# Sensors5V.net
KiCad netlist of a schematic drawn in Altium Designer
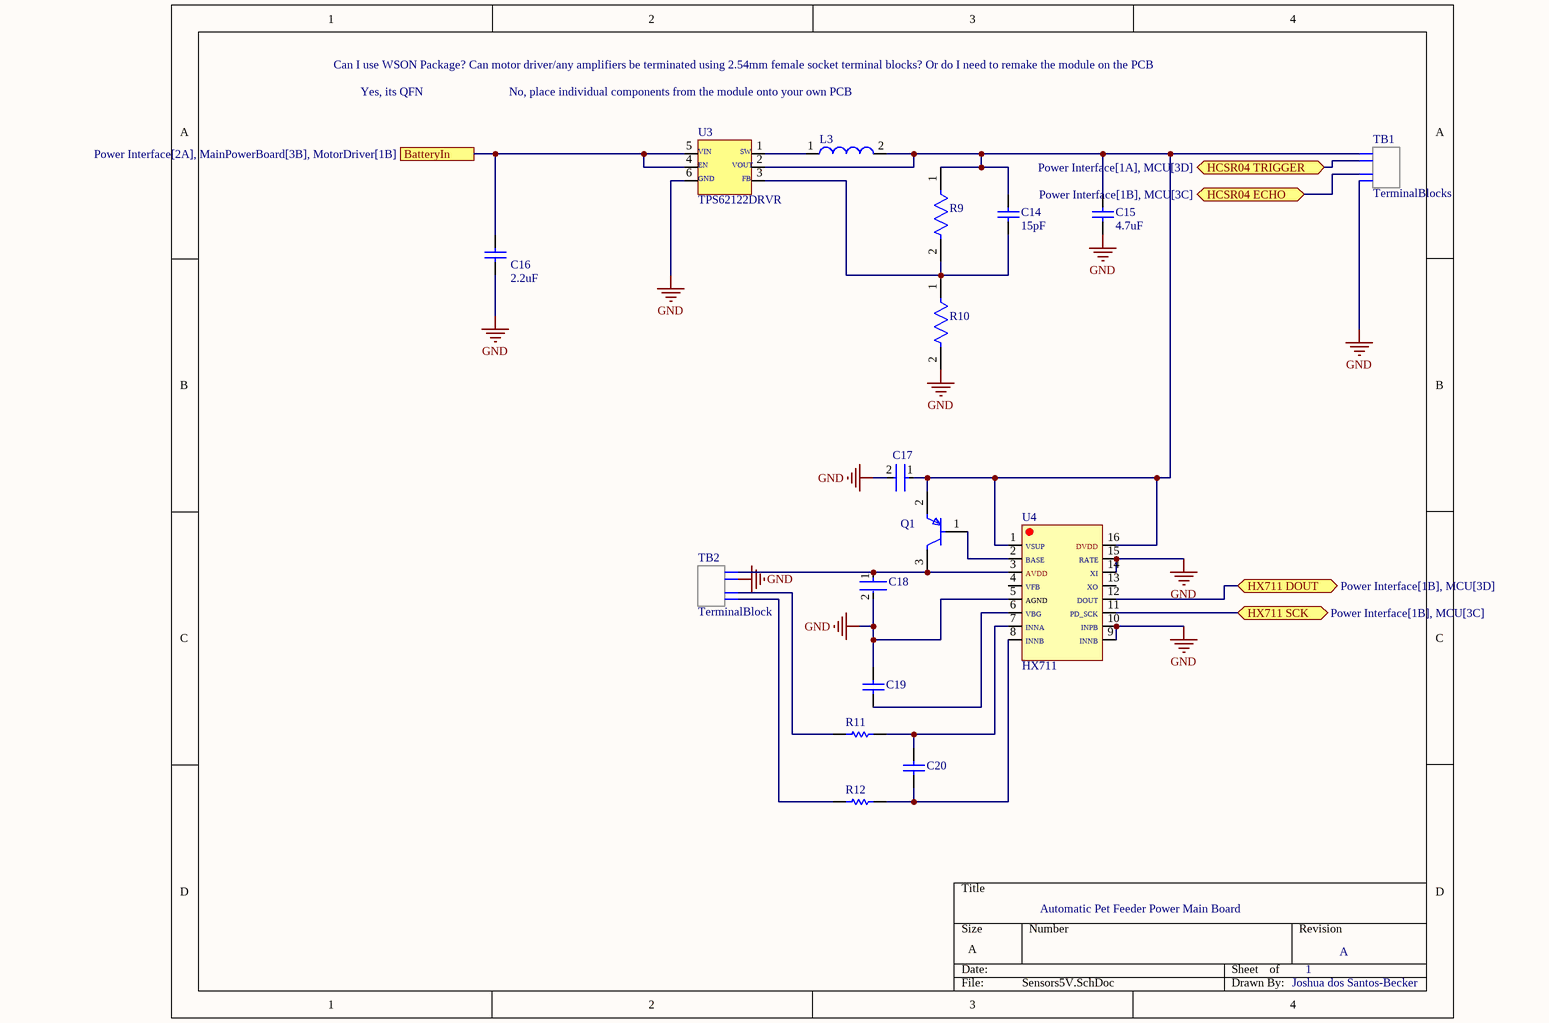
[diagram p0: Sensors5V.SchDoc]

(export (version "E")
  (design (tool "Eeschema 10.0.6"))
  (components
    (comp (ref "C14")
      (value "15pF")
      (footprint "CAP_0805")
      (description "CC0805JRNPO9BN150")
      (libsource (lib "gsl") (part "Cff"))
    )
    (comp (ref "C15")
      (value "4.7uF")
      (footprint "CAPC1005X06N")
      (description "GRM155R61A475MEAAD")
      (libsource (lib "gsl") (part "Cout2"))
    )
    (comp (ref "C16")
      (value "2.2uF")
      (footprint "CAPC0402X02N")
      (description "C1005X5R1V225K050BC")
      (libsource (lib "gsl") (part "Cin2"))
    )
    (comp (ref "C17")
      (value "GRM21BR61C106KE15L")
      (footprint "FP-GRM21B-0_1-IPC_C")
      (description "Chip Multilayer Ceramic Capacitors for General Purpose, 0805, 10uF, X5R, 15%, 10%, 16V")
      (fields (field (name "TOLERANCE") "10%") (field (name "VOLTAGE") "16V"))
      (libsource (lib "Altium Content Vault") (part "b4654b650e69147ec39a6b967a45e02"))
    )
    (comp (ref "C18")
      (value "GRM21BR61C106KE15L")
      (footprint "FP-GRM21B-0_1-IPC_C")
      (description "Chip Multilayer Ceramic Capacitors for General Purpose, 0805, 10uF, X5R, 15%, 10%, 16V")
      (fields (field (name "TOLERANCE") "10%") (field (name "VOLTAGE") "16V"))
      (libsource (lib "Altium Content Vault") (part "b4654b650e69147ec39a6b967a45e02"))
    )
    (comp (ref "C19")
      (value "GRM033C71C104KE14J")
      (footprint "CAPC0603X33N")
      (fields (field (name "MOUSER PART NUMBER") "81-GRM033C71C104KE4J"))
      (libsource (lib "gsl") (part "0.1uF"))
    )
    (comp (ref "C20")
      (value "GRM033C71C104KE14J")
      (footprint "CAPC0603X33N")
      (fields (field (name "MOUSER PART NUMBER") "81-GRM033C71C104KE4J"))
      (libsource (lib "gsl") (part "0.1uF"))
    )
    (comp (ref "L3")
      (value "~")
      (footprint "FP-CB2012-IPC_A")
      (description "CBC2012T220M")
      (fields (field (name "TOLERANCE") "20%"))
      (libsource (lib "gsl") (part "L1"))
    )
    (comp (ref "Q1")
      (value "MMSS8550-H-TP")
      (footprint "FP-SOT-23-IPC_B")
      (description "TRANS PNP 25V 1.5A SOT23")
      (libsource (lib "Altium Content Vault") (part "0e8486ed3b47d9c69b8404ba87cf0f7"))
    )
    (comp (ref "R9")
      (value "~")
      (footprint "RESC0603(1608)_N")
      (description "RC0603FR-07430KL")
      (fields (field (name "POWER") "0.1 W") (field (name "TOLERANCE") "1 %"))
      (libsource (lib "gsl") (part "RES"))
    )
    (comp (ref "R10")
      (value "~")
      (footprint "RESC1608X55X25LL10T15")
      (description "RC0603FR-0782KL")
      (fields (field (name "MANUFACTURER") "Yageo") (field (name "TOLERANCE") "1%"))
      (libsource (lib "gsl") (part "RES-2"))
    )
    (comp (ref "R11")
      (value "ERJ-2RKF1000X")
      (footprint "RESC1005X40X25LL05T05")
      (description "Chip Resistor, 100 Ohm, +/- 1%, 100 mW, -55 to 155 degC, 0402 (1005 Metric), RoHS, Tape and Reel")
      (fields (field (name "MANUFACTURER") "Basic Passives") (field (name "TOLERANCE") "1%"))
      (libsource (lib "Altium Content Vault") (part "RES-2"))
    )
    (comp (ref "R12")
      (value "ERJ-2RKF1000X")
      (footprint "RESC1005X40X25LL05T05")
      (description "Chip Resistor, 100 Ohm, +/- 1%, 100 mW, -55 to 155 degC, 0402 (1005 Metric), RoHS, Tape and Reel")
      (fields (field (name "MANUFACTURER") "Basic Passives") (field (name "TOLERANCE") "1%"))
      (libsource (lib "Altium Content Vault") (part "RES-2"))
    )
    (comp (ref "TB1")
      (value "TerminalBlocks")
      (footprint "PHOENIX_1725672")
      (libsource (lib "gsl") (part "TerminalBlock"))
    )
    (comp (ref "TB2")
      (value "TerminalBlock")
      (footprint "PHOENIX_1725672")
      (libsource (lib "") (part "TerminalBlock_1"))
    )
    (comp (ref "U3")
      (value "TPS62122DRVR")
      (footprint "PSON65P200X80_HS-7N")
      (libsource (lib "gsl") (part "TPS6212"))
    )
    (comp (ref "U4") (value "HX711") (footprint "TSOP127P600X160-16N") (libsource (lib "gsl") (part "HX711")))
  )
  (nets
    (net (code "1") (name "/BatteryIn") (class "Default")
      (node (ref "C16") (pin "2") (pinfunction "2_2") (pintype "passive"))
      (node (ref "U3") (pin "4") (pinfunction "4_4") (pintype "passive"))
      (node (ref "U3") (pin "5") (pinfunction "5_5") (pintype "passive"))
    )
    (net (code "2") (name "/HCSR04 ECHO") (class "Default")
      (node (ref "TB1") (pin "3") (pinfunction "3_3") (pintype "passive"))
    )
    (net (code "3") (name "/HCSR04 TRIGGER") (class "Default")
      (node (ref "TB1") (pin "2") (pinfunction "2_2") (pintype "passive"))
    )
    (net (code "4") (name "/HX711 DOUT") (class "Default")
      (node (ref "U4") (pin "12") (pinfunction "12_12") (pintype "passive"))
    )
    (net (code "5") (name "/HX711 SCK") (class "Default")
      (node (ref "U4") (pin "11") (pinfunction "11_11") (pintype "passive"))
    )
    (net (code "6") (name "GND") (class "Default")
      (node (ref "C15") (pin "1") (pinfunction "1_1") (pintype "passive"))
      (node (ref "C16") (pin "1") (pinfunction "1_1") (pintype "passive"))
      (node (ref "C17") (pin "2") (pinfunction "2_2") (pintype "passive"))
      (node (ref "C18") (pin "2") (pinfunction "2_2") (pintype "passive"))
      (node (ref "C19") (pin "2") (pinfunction "2_2") (pintype "passive"))
      (node (ref "R10") (pin "2") (pinfunction "2_2") (pintype "passive"))
      (node (ref "TB1") (pin "4") (pinfunction "4_4") (pintype "passive"))
      (node (ref "TB2") (pin "3") (pinfunction "3_3") (pintype "passive"))
      (node (ref "U3") (pin "6") (pinfunction "6_6") (pintype "passive"))
      (node (ref "U4") (pin "10") (pinfunction "10_10") (pintype "passive"))
      (node (ref "U4") (pin "14") (pinfunction "14_14") (pintype "passive"))
      (node (ref "U4") (pin "15") (pinfunction "15_15") (pintype "passive"))
      (node (ref "U4") (pin "5") (pinfunction "5_5") (pintype "passive"))
      (node (ref "U4") (pin "9") (pinfunction "9_9") (pintype "passive"))
    )
    (net (code "7") (name "Net-(C14-Pad1)") (class "Default")
      (node (ref "C14") (pin "1") (pinfunction "1_1") (pintype "passive"))
      (node (ref "R10") (pin "1") (pinfunction "1_1") (pintype "passive"))
      (node (ref "R9") (pin "2") (pinfunction "2_2") (pintype "passive"))
      (node (ref "U3") (pin "3") (pinfunction "3_3") (pintype "passive"))
    )
    (net (code "8") (name "Net-(C19-Pad1)") (class "Default")
      (node (ref "C19") (pin "1") (pinfunction "1_1") (pintype "passive"))
      (node (ref "U4") (pin "6") (pinfunction "6_6") (pintype "passive"))
    )
    (net (code "9") (name "Net-(C20-Pad1)") (class "Default")
      (node (ref "C20") (pin "1") (pinfunction "1_1") (pintype "passive"))
      (node (ref "R12") (pin "2") (pinfunction "2_2") (pintype "passive"))
      (node (ref "U4") (pin "8") (pinfunction "8_8") (pintype "passive"))
    )
    (net (code "10") (name "Net-(C20-Pad2)") (class "Default")
      (node (ref "C20") (pin "2") (pinfunction "2_2") (pintype "passive"))
      (node (ref "R11") (pin "2") (pinfunction "2_2") (pintype "passive"))
      (node (ref "U4") (pin "7") (pinfunction "7_7") (pintype "passive"))
    )
    (net (code "11") (name "Net-(L3-Pad1)") (class "Default")
      (node (ref "L3") (pin "1") (pinfunction "1_1") (pintype "passive"))
      (node (ref "U3") (pin "1") (pinfunction "1_1") (pintype "passive"))
    )
    (net (code "12") (name "Net-(Q1-B)") (class "Default")
      (node (ref "Q1") (pin "1") (pinfunction "B_1") (pintype "passive"))
      (node (ref "U4") (pin "2") (pinfunction "2_2") (pintype "passive"))
    )
    (net (code "13") (name "Net-(Q1-C)") (class "Default")
      (node (ref "C18") (pin "1") (pinfunction "1_1") (pintype "passive"))
      (node (ref "Q1") (pin "3") (pinfunction "C_3") (pintype "passive"))
      (node (ref "TB2") (pin "4") (pinfunction "4_4") (pintype "passive"))
      (node (ref "U4") (pin "3") (pinfunction "3_3") (pintype "passive"))
    )
    (net (code "14") (name "Net-(Q1-E)") (class "Default")
      (node (ref "C14") (pin "2") (pinfunction "2_2") (pintype "passive"))
      (node (ref "C15") (pin "2") (pinfunction "2_2") (pintype "passive"))
      (node (ref "C17") (pin "1") (pinfunction "1_1") (pintype "passive"))
      (node (ref "L3") (pin "2") (pinfunction "2_2") (pintype "passive"))
      (node (ref "Q1") (pin "2") (pinfunction "E_2") (pintype "passive"))
      (node (ref "R9") (pin "1") (pinfunction "1_1") (pintype "passive"))
      (node (ref "TB1") (pin "1") (pinfunction "1_1") (pintype "passive"))
      (node (ref "U3") (pin "2") (pinfunction "2_2") (pintype "passive"))
      (node (ref "U4") (pin "1") (pinfunction "1_1") (pintype "passive"))
      (node (ref "U4") (pin "16") (pinfunction "16_16") (pintype "passive"))
    )
    (net (code "15") (name "Net-(R11-Pad1)") (class "Default")
      (node (ref "R11") (pin "1") (pinfunction "1_1") (pintype "passive"))
      (node (ref "TB2") (pin "2") (pinfunction "2_2") (pintype "passive"))
    )
    (net (code "16") (name "Net-(R12-Pad1)") (class "Default")
      (node (ref "R12") (pin "1") (pinfunction "1_1") (pintype "passive"))
      (node (ref "TB2") (pin "1") (pinfunction "1_1") (pintype "passive"))
    )
    (net (code "17") (name "unconnected-(U4-Pad4)") (class "Default")
      (node (ref "U4") (pin "4") (pinfunction "4_4") (pintype "passive"))
    )
    (net (code "18") (name "unconnected-(U4-Pad13)") (class "Default")
      (node (ref "U4") (pin "13") (pinfunction "13_13") (pintype "passive"))
    )
  )
)
